# esquema.net
KiCad netlist of a schematic drawn in EAGLE
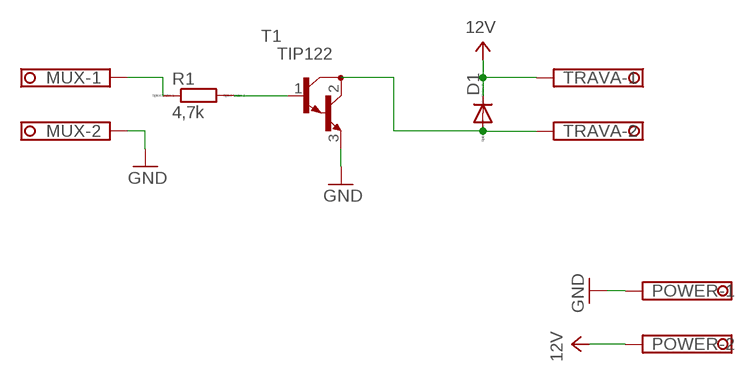
[diagram p0: schematic, sheet 1]

(export (version "E")
  (design (tool "Eeschema 10.0.6"))
  (components
    (comp (ref "D1")
      (value "1N4004")
      (footprint "eagle-import:DO41-10")
      (libsource (lib "eagle-import") (part "1N4004"))
    )
    (comp (ref "MUX")
      (value "TERMINAL-BLOCK-3.5MM-2-PIN-ROUND-PAD")
      (footprint "eagle-import:TERMINAL-BLOCK-2-PIN-3.5MM-ROUND-PAD")
      (libsource (lib "eagle-import") (part "TERMINAL-BLOCK-3.5MM-2-PIN-ROUND-PAD"))
    )
    (comp (ref "POWER")
      (value "TERMINAL-BLOCK-3.5MM-2-PIN-ROUND-PAD")
      (footprint "eagle-import:TERMINAL-BLOCK-2-PIN-3.5MM-ROUND-PAD")
      (libsource (lib "eagle-import") (part "TERMINAL-BLOCK-3.5MM-2-PIN-ROUND-PAD"))
    )
    (comp (ref "R1")
      (value "4,7k")
      (footprint "eagle-import:0207_10")
      (libsource (lib "eagle-import") (part "R0207/10"))
    )
    (comp (ref "T1")
      (value "TIP122")
      (footprint "eagle-import:TO220")
      (libsource (lib "eagle-import") (part "TIP122"))
    )
    (comp (ref "TRAVA")
      (value "TERMINAL-BLOCK-3.5MM-2-PIN-ROUND-PAD")
      (footprint "eagle-import:TERMINAL-BLOCK-2-PIN-3.5MM-ROUND-PAD")
      (libsource (lib "eagle-import") (part "TERMINAL-BLOCK-3.5MM-2-PIN-ROUND-PAD"))
    )
  )
  (nets
    (net (code "1") (name "12V") (class "Default")
      (node (ref "D1") (pin "C") (pinfunction "C_C") (pintype "passive"))
      (node (ref "POWER") (pin "2") (pinfunction "K_2") (pintype "passive"))
      (node (ref "TRAVA") (pin "1") (pinfunction "K_1") (pintype "passive"))
    )
    (net (code "2") (name "GND") (class "Default")
      (node (ref "MUX") (pin "2") (pinfunction "K_2") (pintype "passive"))
      (node (ref "POWER") (pin "1") (pinfunction "K_1") (pintype "passive"))
      (node (ref "T1") (pin "3") (pinfunction "E_3") (pintype "passive"))
    )
    (net (code "3") (name "Net-(MUXA-K)") (class "Default")
      (node (ref "MUX") (pin "1") (pinfunction "K_1") (pintype "passive"))
      (node (ref "R1") (pin "1") (pinfunction "1_1") (pintype "passive"))
    )
    (net (code "4") (name "Net-(T1-B)") (class "Default")
      (node (ref "R1") (pin "2") (pinfunction "2_2") (pintype "passive"))
      (node (ref "T1") (pin "1") (pinfunction "B_1") (pintype "passive"))
    )
    (net (code "5") (name "Net-(T1-C)") (class "Default")
      (node (ref "D1") (pin "A") (pinfunction "A_A") (pintype "passive"))
      (node (ref "T1") (pin "2") (pinfunction "C_2") (pintype "passive"))
      (node (ref "TRAVA") (pin "2") (pinfunction "K_2") (pintype "passive"))
    )
  )
)
